# MacropadSchmatic.net
KiCad netlist of a schematic drawn in Altium Designer
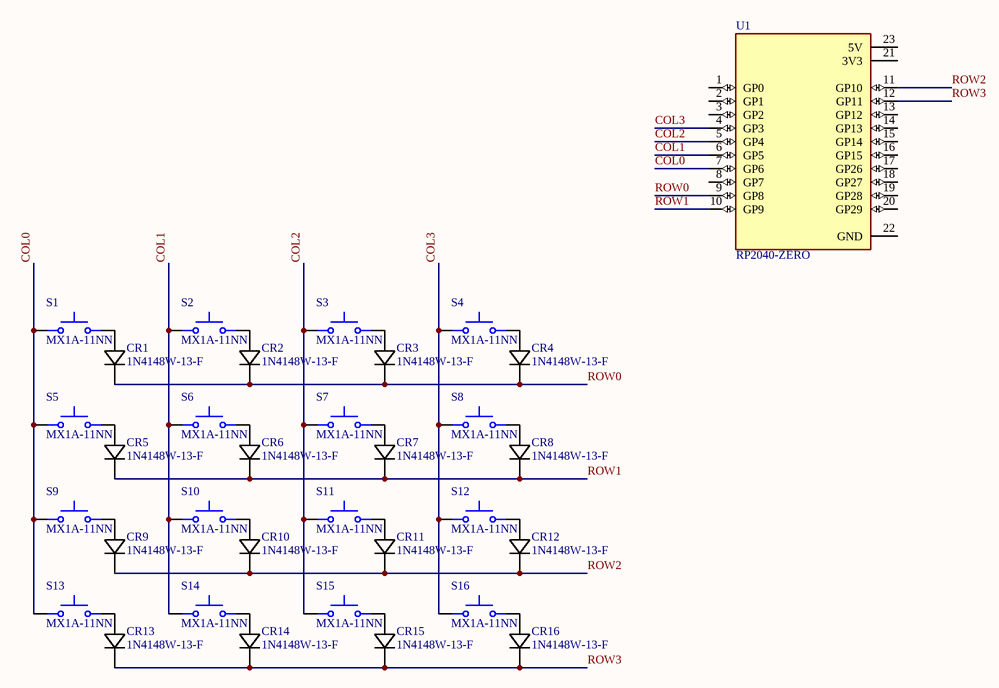
[diagram p0: MacropadSchmatic.SchDoc]

(export (version "E")
  (design (tool "Eeschema 10.0.6"))
  (components
    (comp (ref "CR1")
      (value "1N4148W-13-F")
      (footprint "SOD123_DIO")
      (description "Description")
      (fields (field (name "COPYRIGHT") "Copyright (C) 2025 Ultra Librarian. All rights reserved."))
      (libsource (lib "MRacing FSAE") (part "1N4148W-13-F"))
    )
    (comp (ref "CR2")
      (value "1N4148W-13-F")
      (footprint "SOD123_DIO")
      (description "Description")
      (fields (field (name "COPYRIGHT") "Copyright (C) 2025 Ultra Librarian. All rights reserved."))
      (libsource (lib "MRacing FSAE") (part "1N4148W-13-F"))
    )
    (comp (ref "CR3")
      (value "1N4148W-13-F")
      (footprint "SOD123_DIO")
      (description "Description")
      (fields (field (name "COPYRIGHT") "Copyright (C) 2025 Ultra Librarian. All rights reserved."))
      (libsource (lib "MRacing FSAE") (part "1N4148W-13-F"))
    )
    (comp (ref "CR4")
      (value "1N4148W-13-F")
      (footprint "SOD123_DIO")
      (description "Description")
      (fields (field (name "COPYRIGHT") "Copyright (C) 2025 Ultra Librarian. All rights reserved."))
      (libsource (lib "MRacing FSAE") (part "1N4148W-13-F"))
    )
    (comp (ref "CR5")
      (value "1N4148W-13-F")
      (footprint "SOD123_DIO")
      (description "Description")
      (fields (field (name "COPYRIGHT") "Copyright (C) 2025 Ultra Librarian. All rights reserved."))
      (libsource (lib "MRacing FSAE") (part "1N4148W-13-F"))
    )
    (comp (ref "CR6")
      (value "1N4148W-13-F")
      (footprint "SOD123_DIO")
      (description "Description")
      (fields (field (name "COPYRIGHT") "Copyright (C) 2025 Ultra Librarian. All rights reserved."))
      (libsource (lib "MRacing FSAE") (part "1N4148W-13-F"))
    )
    (comp (ref "CR7")
      (value "1N4148W-13-F")
      (footprint "SOD123_DIO")
      (description "Description")
      (fields (field (name "COPYRIGHT") "Copyright (C) 2025 Ultra Librarian. All rights reserved."))
      (libsource (lib "MRacing FSAE") (part "1N4148W-13-F"))
    )
    (comp (ref "CR8")
      (value "1N4148W-13-F")
      (footprint "SOD123_DIO")
      (description "Description")
      (fields (field (name "COPYRIGHT") "Copyright (C) 2025 Ultra Librarian. All rights reserved."))
      (libsource (lib "MRacing FSAE") (part "1N4148W-13-F"))
    )
    (comp (ref "CR9")
      (value "1N4148W-13-F")
      (footprint "SOD123_DIO")
      (description "Description")
      (fields (field (name "COPYRIGHT") "Copyright (C) 2025 Ultra Librarian. All rights reserved."))
      (libsource (lib "MRacing FSAE") (part "1N4148W-13-F"))
    )
    (comp (ref "CR10")
      (value "1N4148W-13-F")
      (footprint "SOD123_DIO")
      (description "Description")
      (fields (field (name "COPYRIGHT") "Copyright (C) 2025 Ultra Librarian. All rights reserved."))
      (libsource (lib "MRacing FSAE") (part "1N4148W-13-F"))
    )
    (comp (ref "CR11")
      (value "1N4148W-13-F")
      (footprint "SOD123_DIO")
      (description "Description")
      (fields (field (name "COPYRIGHT") "Copyright (C) 2025 Ultra Librarian. All rights reserved."))
      (libsource (lib "MRacing FSAE") (part "1N4148W-13-F"))
    )
    (comp (ref "CR12")
      (value "1N4148W-13-F")
      (footprint "SOD123_DIO")
      (description "Description")
      (fields (field (name "COPYRIGHT") "Copyright (C) 2025 Ultra Librarian. All rights reserved."))
      (libsource (lib "MRacing FSAE") (part "1N4148W-13-F"))
    )
    (comp (ref "CR13")
      (value "1N4148W-13-F")
      (footprint "SOD123_DIO")
      (description "Description")
      (fields (field (name "COPYRIGHT") "Copyright (C) 2025 Ultra Librarian. All rights reserved."))
      (libsource (lib "MRacing FSAE") (part "1N4148W-13-F"))
    )
    (comp (ref "CR14")
      (value "1N4148W-13-F")
      (footprint "SOD123_DIO")
      (description "Description")
      (fields (field (name "COPYRIGHT") "Copyright (C) 2025 Ultra Librarian. All rights reserved."))
      (libsource (lib "MRacing FSAE") (part "1N4148W-13-F"))
    )
    (comp (ref "CR15")
      (value "1N4148W-13-F")
      (footprint "SOD123_DIO")
      (description "Description")
      (fields (field (name "COPYRIGHT") "Copyright (C) 2025 Ultra Librarian. All rights reserved."))
      (libsource (lib "MRacing FSAE") (part "1N4148W-13-F"))
    )
    (comp (ref "CR16")
      (value "1N4148W-13-F")
      (footprint "SOD123_DIO")
      (description "Description")
      (fields (field (name "COPYRIGHT") "Copyright (C) 2025 Ultra Librarian. All rights reserved."))
      (libsource (lib "MRacing FSAE") (part "1N4148W-13-F"))
    )
    (comp (ref "S1")
      (value "MX1A-11NN")
      (footprint "SW_MX1A-11NN")
      (description "Switch,Key,SPST-NO,Keyboard,Low Profile,10mA,12VDC,Face Place Mount,Std Force")
      (fields (field (name "MF") "Cherry"))
      (libsource (lib "MRacing FSAE") (part "MX1A-11NN"))
    )
    (comp (ref "S2")
      (value "MX1A-11NN")
      (footprint "SW_MX1A-11NN")
      (description "Switch,Key,SPST-NO,Keyboard,Low Profile,10mA,12VDC,Face Place Mount,Std Force")
      (fields (field (name "MF") "Cherry"))
      (libsource (lib "MRacing FSAE") (part "MX1A-11NN"))
    )
    (comp (ref "S3")
      (value "MX1A-11NN")
      (footprint "SW_MX1A-11NN")
      (description "Switch,Key,SPST-NO,Keyboard,Low Profile,10mA,12VDC,Face Place Mount,Std Force")
      (fields (field (name "MF") "Cherry"))
      (libsource (lib "MRacing FSAE") (part "MX1A-11NN"))
    )
    (comp (ref "S4")
      (value "MX1A-11NN")
      (footprint "SW_MX1A-11NN")
      (description "Switch,Key,SPST-NO,Keyboard,Low Profile,10mA,12VDC,Face Place Mount,Std Force")
      (fields (field (name "MF") "Cherry"))
      (libsource (lib "MRacing FSAE") (part "MX1A-11NN"))
    )
    (comp (ref "S5")
      (value "MX1A-11NN")
      (footprint "SW_MX1A-11NN")
      (description "Switch,Key,SPST-NO,Keyboard,Low Profile,10mA,12VDC,Face Place Mount,Std Force")
      (fields (field (name "MF") "Cherry"))
      (libsource (lib "MRacing FSAE") (part "MX1A-11NN"))
    )
    (comp (ref "S6")
      (value "MX1A-11NN")
      (footprint "SW_MX1A-11NN")
      (description "Switch,Key,SPST-NO,Keyboard,Low Profile,10mA,12VDC,Face Place Mount,Std Force")
      (fields (field (name "MF") "Cherry"))
      (libsource (lib "MRacing FSAE") (part "MX1A-11NN"))
    )
    (comp (ref "S7")
      (value "MX1A-11NN")
      (footprint "SW_MX1A-11NN")
      (description "Switch,Key,SPST-NO,Keyboard,Low Profile,10mA,12VDC,Face Place Mount,Std Force")
      (fields (field (name "MF") "Cherry"))
      (libsource (lib "MRacing FSAE") (part "MX1A-11NN"))
    )
    (comp (ref "S8")
      (value "MX1A-11NN")
      (footprint "SW_MX1A-11NN")
      (description "Switch,Key,SPST-NO,Keyboard,Low Profile,10mA,12VDC,Face Place Mount,Std Force")
      (fields (field (name "MF") "Cherry"))
      (libsource (lib "MRacing FSAE") (part "MX1A-11NN"))
    )
    (comp (ref "S9")
      (value "MX1A-11NN")
      (footprint "SW_MX1A-11NN")
      (description "Switch,Key,SPST-NO,Keyboard,Low Profile,10mA,12VDC,Face Place Mount,Std Force")
      (fields (field (name "MF") "Cherry"))
      (libsource (lib "MRacing FSAE") (part "MX1A-11NN"))
    )
    (comp (ref "S10")
      (value "MX1A-11NN")
      (footprint "SW_MX1A-11NN")
      (description "Switch,Key,SPST-NO,Keyboard,Low Profile,10mA,12VDC,Face Place Mount,Std Force")
      (fields (field (name "MF") "Cherry"))
      (libsource (lib "MRacing FSAE") (part "MX1A-11NN"))
    )
    (comp (ref "S11")
      (value "MX1A-11NN")
      (footprint "SW_MX1A-11NN")
      (description "Switch,Key,SPST-NO,Keyboard,Low Profile,10mA,12VDC,Face Place Mount,Std Force")
      (fields (field (name "MF") "Cherry"))
      (libsource (lib "MRacing FSAE") (part "MX1A-11NN"))
    )
    (comp (ref "S12")
      (value "MX1A-11NN")
      (footprint "SW_MX1A-11NN")
      (description "Switch,Key,SPST-NO,Keyboard,Low Profile,10mA,12VDC,Face Place Mount,Std Force")
      (fields (field (name "MF") "Cherry"))
      (libsource (lib "MRacing FSAE") (part "MX1A-11NN"))
    )
    (comp (ref "S13")
      (value "MX1A-11NN")
      (footprint "SW_MX1A-11NN")
      (description "Switch,Key,SPST-NO,Keyboard,Low Profile,10mA,12VDC,Face Place Mount,Std Force")
      (fields (field (name "MF") "Cherry"))
      (libsource (lib "MRacing FSAE") (part "MX1A-11NN"))
    )
    (comp (ref "S14")
      (value "MX1A-11NN")
      (footprint "SW_MX1A-11NN")
      (description "Switch,Key,SPST-NO,Keyboard,Low Profile,10mA,12VDC,Face Place Mount,Std Force")
      (fields (field (name "MF") "Cherry"))
      (libsource (lib "MRacing FSAE") (part "MX1A-11NN"))
    )
    (comp (ref "S15")
      (value "MX1A-11NN")
      (footprint "SW_MX1A-11NN")
      (description "Switch,Key,SPST-NO,Keyboard,Low Profile,10mA,12VDC,Face Place Mount,Std Force")
      (fields (field (name "MF") "Cherry"))
      (libsource (lib "MRacing FSAE") (part "MX1A-11NN"))
    )
    (comp (ref "S16")
      (value "MX1A-11NN")
      (footprint "SW_MX1A-11NN")
      (description "Switch,Key,SPST-NO,Keyboard,Low Profile,10mA,12VDC,Face Place Mount,Std Force")
      (fields (field (name "MF") "Cherry"))
      (libsource (lib "MRacing FSAE") (part "MX1A-11NN"))
    )
    (comp (ref "U1")
      (value "RP2040-ZERO")
      (footprint "MODULE_RP2040-ZERO")
      (description "Low-Cost, High-Performance Pico-Like MCU Board Based On Raspberry Pi Microcontroller RP2040")
      (fields (field (name "MF") "Waveshare Electronics"))
      (libsource (lib "MRacing FSAE") (part "RP2040-ZERO"))
    )
  )
  (nets
    (net (code "1") (name "/COL0") (class "Default")
      (node (ref "S1") (pin "1") (pinfunction "1_1") (pintype "passive"))
      (node (ref "S13") (pin "1") (pinfunction "1_1") (pintype "passive"))
      (node (ref "S5") (pin "1") (pinfunction "1_1") (pintype "passive"))
      (node (ref "S9") (pin "1") (pinfunction "1_1") (pintype "passive"))
      (node (ref "U1") (pin "7") (pinfunction "GP6_7") (pintype "bidirectional"))
    )
    (net (code "2") (name "/COL1") (class "Default")
      (node (ref "S10") (pin "1") (pinfunction "1_1") (pintype "passive"))
      (node (ref "S14") (pin "1") (pinfunction "1_1") (pintype "passive"))
      (node (ref "S2") (pin "1") (pinfunction "1_1") (pintype "passive"))
      (node (ref "S6") (pin "1") (pinfunction "1_1") (pintype "passive"))
      (node (ref "U1") (pin "6") (pinfunction "GP5_6") (pintype "bidirectional"))
    )
    (net (code "3") (name "/COL2") (class "Default")
      (node (ref "S11") (pin "1") (pinfunction "1_1") (pintype "passive"))
      (node (ref "S15") (pin "1") (pinfunction "1_1") (pintype "passive"))
      (node (ref "S3") (pin "1") (pinfunction "1_1") (pintype "passive"))
      (node (ref "S7") (pin "1") (pinfunction "1_1") (pintype "passive"))
      (node (ref "U1") (pin "5") (pinfunction "GP4_5") (pintype "bidirectional"))
    )
    (net (code "4") (name "/COL3") (class "Default")
      (node (ref "S12") (pin "1") (pinfunction "1_1") (pintype "passive"))
      (node (ref "S16") (pin "1") (pinfunction "1_1") (pintype "passive"))
      (node (ref "S4") (pin "1") (pinfunction "1_1") (pintype "passive"))
      (node (ref "S8") (pin "1") (pinfunction "1_1") (pintype "passive"))
      (node (ref "U1") (pin "4") (pinfunction "GP3_4") (pintype "bidirectional"))
    )
    (net (code "5") (name "/ROW0") (class "Default")
      (node (ref "CR1") (pin "1") (pinfunction "1_1") (pintype "passive"))
      (node (ref "CR2") (pin "1") (pinfunction "1_1") (pintype "passive"))
      (node (ref "CR3") (pin "1") (pinfunction "1_1") (pintype "passive"))
      (node (ref "CR4") (pin "1") (pinfunction "1_1") (pintype "passive"))
      (node (ref "U1") (pin "9") (pinfunction "GP8_9") (pintype "bidirectional"))
    )
    (net (code "6") (name "/ROW1") (class "Default")
      (node (ref "CR5") (pin "1") (pinfunction "1_1") (pintype "passive"))
      (node (ref "CR6") (pin "1") (pinfunction "1_1") (pintype "passive"))
      (node (ref "CR7") (pin "1") (pinfunction "1_1") (pintype "passive"))
      (node (ref "CR8") (pin "1") (pinfunction "1_1") (pintype "passive"))
      (node (ref "U1") (pin "10") (pinfunction "GP9_10") (pintype "bidirectional"))
    )
    (net (code "7") (name "/ROW2") (class "Default")
      (node (ref "CR10") (pin "1") (pinfunction "1_1") (pintype "passive"))
      (node (ref "CR11") (pin "1") (pinfunction "1_1") (pintype "passive"))
      (node (ref "CR12") (pin "1") (pinfunction "1_1") (pintype "passive"))
      (node (ref "CR9") (pin "1") (pinfunction "1_1") (pintype "passive"))
      (node (ref "U1") (pin "11") (pinfunction "GP10_11") (pintype "bidirectional"))
    )
    (net (code "8") (name "/ROW3") (class "Default")
      (node (ref "CR13") (pin "1") (pinfunction "1_1") (pintype "passive"))
      (node (ref "CR14") (pin "1") (pinfunction "1_1") (pintype "passive"))
      (node (ref "CR15") (pin "1") (pinfunction "1_1") (pintype "passive"))
      (node (ref "CR16") (pin "1") (pinfunction "1_1") (pintype "passive"))
      (node (ref "U1") (pin "12") (pinfunction "GP11_12") (pintype "bidirectional"))
    )
    (net (code "9") (name "Net-(CR1-Pad2)") (class "Default")
      (node (ref "CR1") (pin "2") (pinfunction "2_2") (pintype "passive"))
      (node (ref "S1") (pin "2") (pinfunction "2_2") (pintype "passive"))
    )
    (net (code "10") (name "Net-(CR2-Pad2)") (class "Default")
      (node (ref "CR2") (pin "2") (pinfunction "2_2") (pintype "passive"))
      (node (ref "S2") (pin "2") (pinfunction "2_2") (pintype "passive"))
    )
    (net (code "11") (name "Net-(CR3-Pad2)") (class "Default")
      (node (ref "CR3") (pin "2") (pinfunction "2_2") (pintype "passive"))
      (node (ref "S3") (pin "2") (pinfunction "2_2") (pintype "passive"))
    )
    (net (code "12") (name "Net-(CR4-Pad2)") (class "Default")
      (node (ref "CR4") (pin "2") (pinfunction "2_2") (pintype "passive"))
      (node (ref "S4") (pin "2") (pinfunction "2_2") (pintype "passive"))
    )
    (net (code "13") (name "Net-(CR5-Pad2)") (class "Default")
      (node (ref "CR5") (pin "2") (pinfunction "2_2") (pintype "passive"))
      (node (ref "S5") (pin "2") (pinfunction "2_2") (pintype "passive"))
    )
    (net (code "14") (name "Net-(CR6-Pad2)") (class "Default")
      (node (ref "CR6") (pin "2") (pinfunction "2_2") (pintype "passive"))
      (node (ref "S6") (pin "2") (pinfunction "2_2") (pintype "passive"))
    )
    (net (code "15") (name "Net-(CR7-Pad2)") (class "Default")
      (node (ref "CR7") (pin "2") (pinfunction "2_2") (pintype "passive"))
      (node (ref "S7") (pin "2") (pinfunction "2_2") (pintype "passive"))
    )
    (net (code "16") (name "Net-(CR8-Pad2)") (class "Default")
      (node (ref "CR8") (pin "2") (pinfunction "2_2") (pintype "passive"))
      (node (ref "S8") (pin "2") (pinfunction "2_2") (pintype "passive"))
    )
    (net (code "17") (name "Net-(CR9-Pad2)") (class "Default")
      (node (ref "CR9") (pin "2") (pinfunction "2_2") (pintype "passive"))
      (node (ref "S9") (pin "2") (pinfunction "2_2") (pintype "passive"))
    )
    (net (code "18") (name "Net-(CR10-Pad2)") (class "Default")
      (node (ref "CR10") (pin "2") (pinfunction "2_2") (pintype "passive"))
      (node (ref "S10") (pin "2") (pinfunction "2_2") (pintype "passive"))
    )
    (net (code "19") (name "Net-(CR11-Pad2)") (class "Default")
      (node (ref "CR11") (pin "2") (pinfunction "2_2") (pintype "passive"))
      (node (ref "S11") (pin "2") (pinfunction "2_2") (pintype "passive"))
    )
    (net (code "20") (name "Net-(CR12-Pad2)") (class "Default")
      (node (ref "CR12") (pin "2") (pinfunction "2_2") (pintype "passive"))
      (node (ref "S12") (pin "2") (pinfunction "2_2") (pintype "passive"))
    )
    (net (code "21") (name "Net-(CR13-Pad2)") (class "Default")
      (node (ref "CR13") (pin "2") (pinfunction "2_2") (pintype "passive"))
      (node (ref "S13") (pin "2") (pinfunction "2_2") (pintype "passive"))
    )
    (net (code "22") (name "Net-(CR14-Pad2)") (class "Default")
      (node (ref "CR14") (pin "2") (pinfunction "2_2") (pintype "passive"))
      (node (ref "S14") (pin "2") (pinfunction "2_2") (pintype "passive"))
    )
    (net (code "23") (name "Net-(CR15-Pad2)") (class "Default")
      (node (ref "CR15") (pin "2") (pinfunction "2_2") (pintype "passive"))
      (node (ref "S15") (pin "2") (pinfunction "2_2") (pintype "passive"))
    )
    (net (code "24") (name "Net-(CR16-Pad2)") (class "Default")
      (node (ref "CR16") (pin "2") (pinfunction "2_2") (pintype "passive"))
      (node (ref "S16") (pin "2") (pinfunction "2_2") (pintype "passive"))
    )
    (net (code "25") (name "unconnected-(U1-3V3-Pad21)") (class "Default")
      (node (ref "U1") (pin "21") (pinfunction "3V3_21") (pintype "power_in"))
    )
    (net (code "26") (name "unconnected-(U1-5V-Pad23)") (class "Default")
      (node (ref "U1") (pin "23") (pinfunction "5V_23") (pintype "power_in"))
    )
    (net (code "27") (name "unconnected-(U1-GND-Pad22)") (class "Default")
      (node (ref "U1") (pin "22") (pinfunction "GND_22") (pintype "power_in"))
    )
    (net (code "28") (name "unconnected-(U1-GP0-Pad1)") (class "Default")
      (node (ref "U1") (pin "1") (pinfunction "GP0_1") (pintype "bidirectional"))
    )
    (net (code "29") (name "unconnected-(U1-GP1-Pad2)") (class "Default")
      (node (ref "U1") (pin "2") (pinfunction "GP1_2") (pintype "bidirectional"))
    )
    (net (code "30") (name "unconnected-(U1-GP2-Pad3)") (class "Default")
      (node (ref "U1") (pin "3") (pinfunction "GP2_3") (pintype "bidirectional"))
    )
    (net (code "31") (name "unconnected-(U1-GP7-Pad8)") (class "Default")
      (node (ref "U1") (pin "8") (pinfunction "GP7_8") (pintype "bidirectional"))
    )
    (net (code "32") (name "unconnected-(U1-GP12-Pad13)") (class "Default")
      (node (ref "U1") (pin "13") (pinfunction "GP12_13") (pintype "bidirectional"))
    )
    (net (code "33") (name "unconnected-(U1-GP13-Pad14)") (class "Default")
      (node (ref "U1") (pin "14") (pinfunction "GP13_14") (pintype "bidirectional"))
    )
    (net (code "34") (name "unconnected-(U1-GP14-Pad15)") (class "Default")
      (node (ref "U1") (pin "15") (pinfunction "GP14_15") (pintype "bidirectional"))
    )
    (net (code "35") (name "unconnected-(U1-GP15-Pad16)") (class "Default")
      (node (ref "U1") (pin "16") (pinfunction "GP15_16") (pintype "bidirectional"))
    )
    (net (code "36") (name "unconnected-(U1-GP26-Pad17)") (class "Default")
      (node (ref "U1") (pin "17") (pinfunction "GP26_17") (pintype "bidirectional"))
    )
    (net (code "37") (name "unconnected-(U1-GP27-Pad18)") (class "Default")
      (node (ref "U1") (pin "18") (pinfunction "GP27_18") (pintype "bidirectional"))
    )
    (net (code "38") (name "unconnected-(U1-GP28-Pad19)") (class "Default")
      (node (ref "U1") (pin "19") (pinfunction "GP28_19") (pintype "bidirectional"))
    )
    (net (code "39") (name "unconnected-(U1-GP29-Pad20)") (class "Default")
      (node (ref "U1") (pin "20") (pinfunction "GP29_20") (pintype "bidirectional"))
    )
  )
)
